# mixer_module.net
KiCad netlist of a schematic drawn in EAGLE
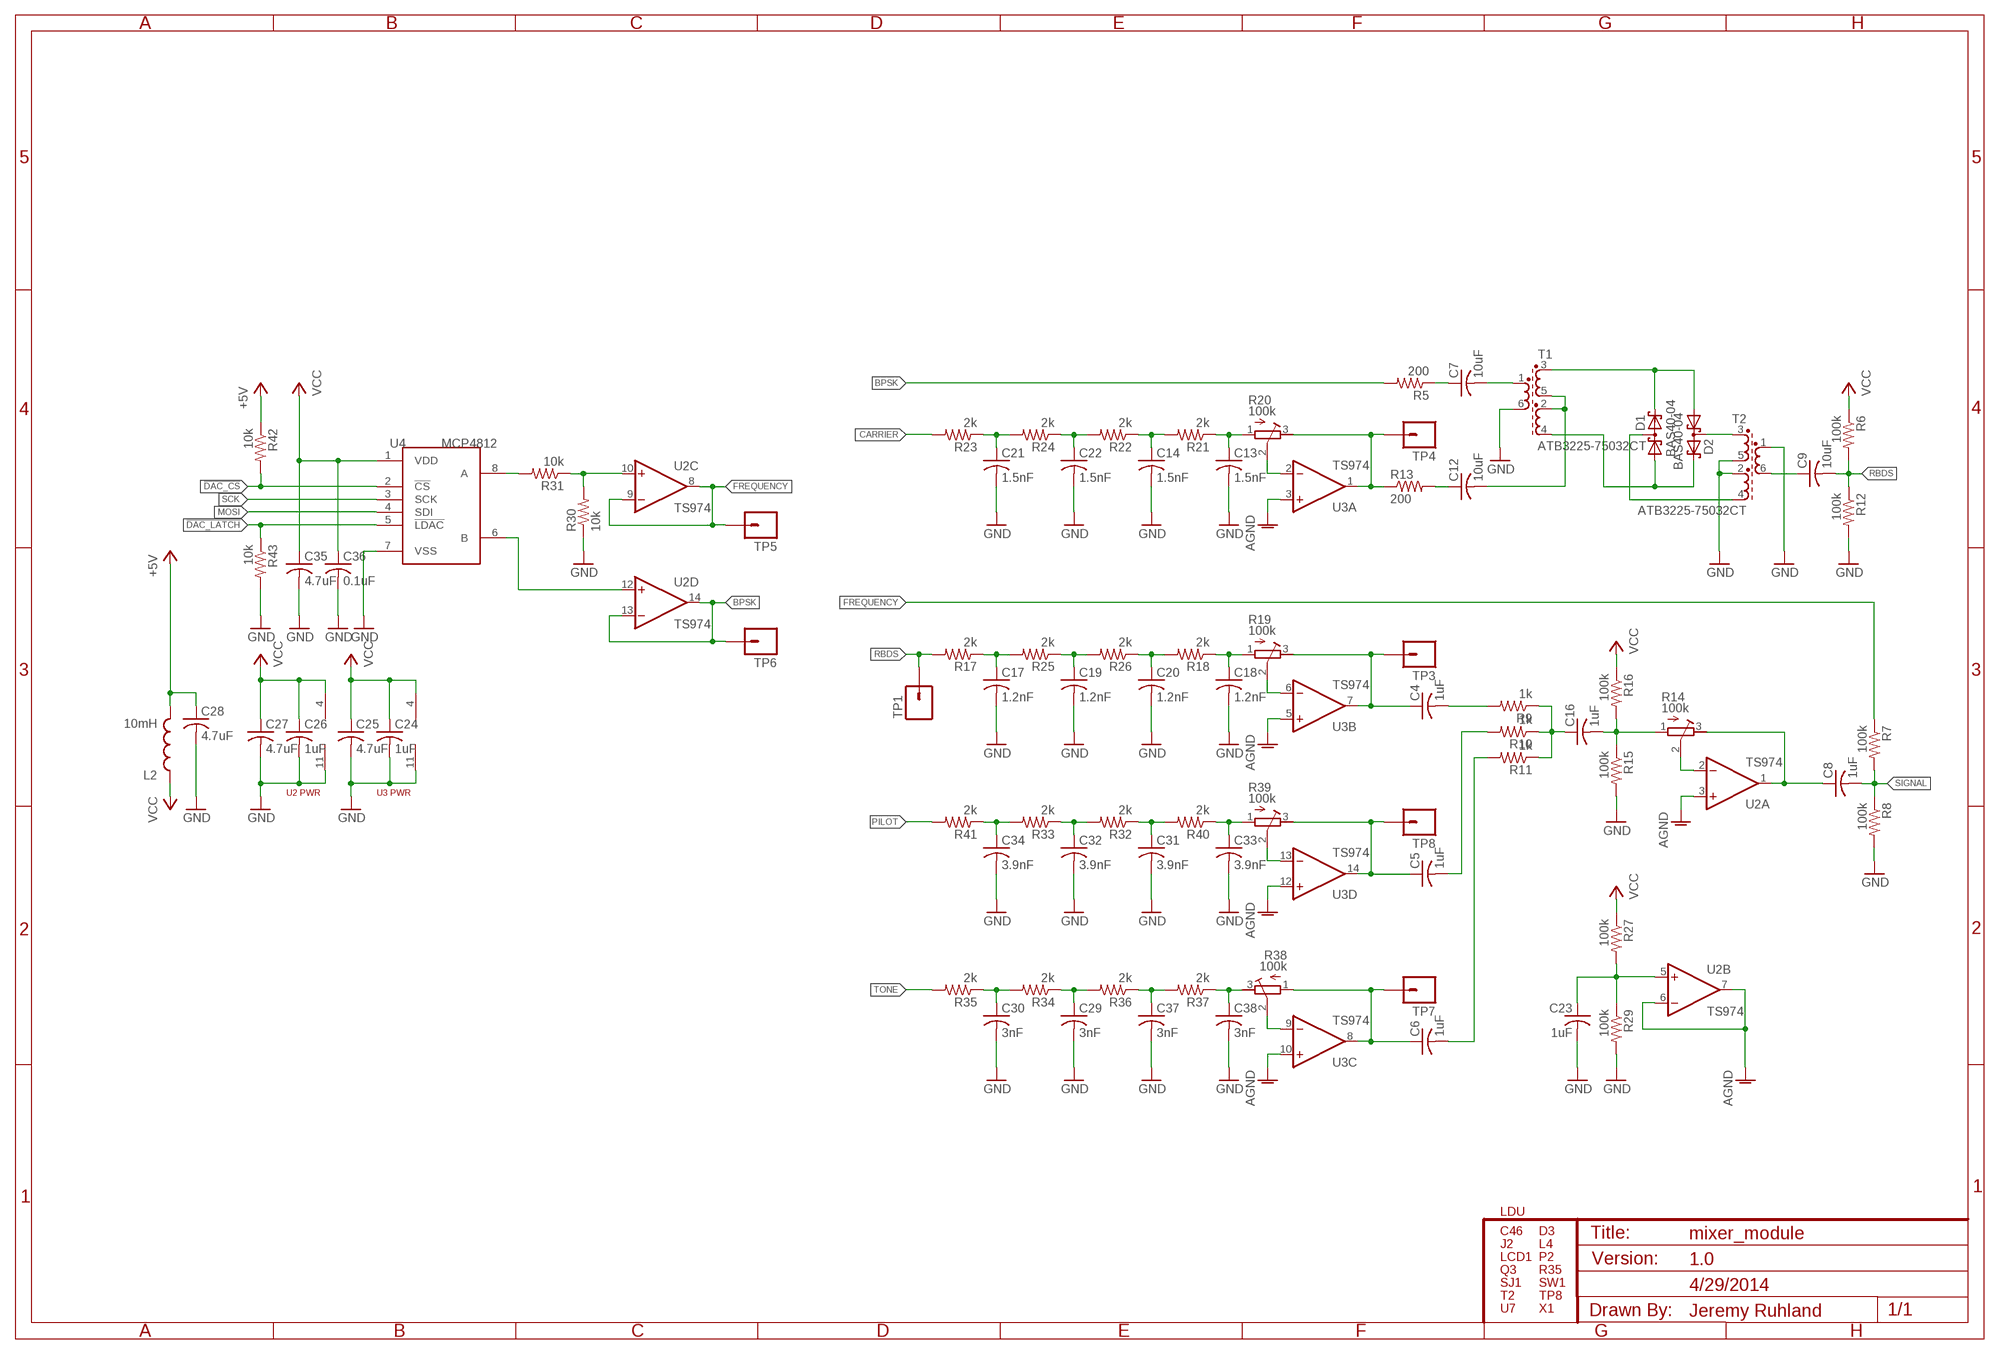
[diagram p0: schematic, sheet 1]

(export (version "E")
  (design (tool "Eeschema 10.0.6"))
  (components
    (comp (ref "C4")
      (value "1uF")
      (footprint "eagle-import:C1206")
      (libsource (lib "eagle-import") (part "C-USC1206"))
    )
    (comp (ref "C5")
      (value "1uF")
      (footprint "eagle-import:C1206")
      (libsource (lib "eagle-import") (part "C-USC1206"))
    )
    (comp (ref "C6")
      (value "1uF")
      (footprint "eagle-import:C1206")
      (libsource (lib "eagle-import") (part "C-USC1206"))
    )
    (comp (ref "C7")
      (value "10uF")
      (footprint "eagle-import:C1206")
      (libsource (lib "eagle-import") (part "C-USC1206"))
    )
    (comp (ref "C8")
      (value "1uF")
      (footprint "eagle-import:C1206")
      (libsource (lib "eagle-import") (part "C-USC1206"))
    )
    (comp (ref "C9")
      (value "10uF")
      (footprint "eagle-import:C1206")
      (libsource (lib "eagle-import") (part "C-USC1206"))
    )
    (comp (ref "C12")
      (value "10uF")
      (footprint "eagle-import:C1206")
      (libsource (lib "eagle-import") (part "C-USC1206"))
    )
    (comp (ref "C13")
      (value "1.5nF")
      (footprint "eagle-import:C1206")
      (libsource (lib "eagle-import") (part "C-USC1206"))
    )
    (comp (ref "C14")
      (value "1.5nF")
      (footprint "eagle-import:C1206")
      (libsource (lib "eagle-import") (part "C-USC1206"))
    )
    (comp (ref "C16")
      (value "1uF")
      (footprint "eagle-import:C1206")
      (libsource (lib "eagle-import") (part "C-USC1206"))
    )
    (comp (ref "C17")
      (value "1.2nF")
      (footprint "eagle-import:C1206")
      (libsource (lib "eagle-import") (part "C-USC1206"))
    )
    (comp (ref "C18")
      (value "1.2nF")
      (footprint "eagle-import:C1206")
      (libsource (lib "eagle-import") (part "C-USC1206"))
    )
    (comp (ref "C19")
      (value "1.2nF")
      (footprint "eagle-import:C1206")
      (libsource (lib "eagle-import") (part "C-USC1206"))
    )
    (comp (ref "C20")
      (value "1.2nF")
      (footprint "eagle-import:C1206")
      (libsource (lib "eagle-import") (part "C-USC1206"))
    )
    (comp (ref "C21")
      (value "1.5nF")
      (footprint "eagle-import:C1206")
      (libsource (lib "eagle-import") (part "C-USC1206"))
    )
    (comp (ref "C22")
      (value "1.5nF")
      (footprint "eagle-import:C1206")
      (libsource (lib "eagle-import") (part "C-USC1206"))
    )
    (comp (ref "C23")
      (value "1uF")
      (footprint "eagle-import:C1206")
      (libsource (lib "eagle-import") (part "C-USC1206"))
    )
    (comp (ref "C24")
      (value "1uF")
      (footprint "eagle-import:C1206")
      (libsource (lib "eagle-import") (part "C-USC1206"))
    )
    (comp (ref "C25")
      (value "4.7uF")
      (footprint "eagle-import:C1206")
      (libsource (lib "eagle-import") (part "C-USC1206"))
    )
    (comp (ref "C26")
      (value "1uF")
      (footprint "eagle-import:C1206")
      (libsource (lib "eagle-import") (part "C-USC1206"))
    )
    (comp (ref "C27")
      (value "4.7uF")
      (footprint "eagle-import:C1206")
      (libsource (lib "eagle-import") (part "C-USC1206"))
    )
    (comp (ref "C28")
      (value "4.7uF")
      (footprint "eagle-import:C1206")
      (libsource (lib "eagle-import") (part "C-USC1206"))
    )
    (comp (ref "C29")
      (value "3nF")
      (footprint "eagle-import:C1206")
      (libsource (lib "eagle-import") (part "C-USC1206"))
    )
    (comp (ref "C30")
      (value "3nF")
      (footprint "eagle-import:C1206")
      (libsource (lib "eagle-import") (part "C-USC1206"))
    )
    (comp (ref "C31")
      (value "3.9nF")
      (footprint "eagle-import:C1206")
      (libsource (lib "eagle-import") (part "C-USC1206"))
    )
    (comp (ref "C32")
      (value "3.9nF")
      (footprint "eagle-import:C1206")
      (libsource (lib "eagle-import") (part "C-USC1206"))
    )
    (comp (ref "C33")
      (value "3.9nF")
      (footprint "eagle-import:C1206")
      (libsource (lib "eagle-import") (part "C-USC1206"))
    )
    (comp (ref "C34")
      (value "3.9nF")
      (footprint "eagle-import:C1206")
      (libsource (lib "eagle-import") (part "C-USC1206"))
    )
    (comp (ref "C35")
      (value "4.7uF")
      (footprint "eagle-import:C1206")
      (libsource (lib "eagle-import") (part "C-USC1206"))
    )
    (comp (ref "C36")
      (value "0.1uF")
      (footprint "eagle-import:C1206")
      (libsource (lib "eagle-import") (part "C-USC1206"))
    )
    (comp (ref "C37")
      (value "3nF")
      (footprint "eagle-import:C1206")
      (libsource (lib "eagle-import") (part "C-USC1206"))
    )
    (comp (ref "C38")
      (value "3nF")
      (footprint "eagle-import:C1206")
      (libsource (lib "eagle-import") (part "C-USC1206"))
    )
    (comp (ref "D1")
      (value "BAS40-04")
      (footprint "eagle-import:SOT23")
      (libsource (lib "eagle-import") (part "BAS40-04"))
    )
    (comp (ref "D2")
      (value "BAS40-04")
      (footprint "eagle-import:SOT23")
      (libsource (lib "eagle-import") (part "BAS40-04"))
    )
    (comp (ref "L2")
      (value "10mH")
      (footprint "eagle-import:1210")
      (libsource (lib "eagle-import") (part "INDUCTOR1210"))
    )
    (comp (ref "R5")
      (value "200")
      (footprint "eagle-import:R1206")
      (libsource (lib "eagle-import") (part "R-US_R1206"))
    )
    (comp (ref "R6")
      (value "100k")
      (footprint "eagle-import:R1206")
      (libsource (lib "eagle-import") (part "R-US_R1206"))
    )
    (comp (ref "R7")
      (value "100k")
      (footprint "eagle-import:R1206")
      (libsource (lib "eagle-import") (part "R-US_R1206"))
    )
    (comp (ref "R8")
      (value "100k")
      (footprint "eagle-import:R1206")
      (libsource (lib "eagle-import") (part "R-US_R1206"))
    )
    (comp (ref "R9")
      (value "1k")
      (footprint "eagle-import:R1206")
      (libsource (lib "eagle-import") (part "R-US_R1206"))
    )
    (comp (ref "R10")
      (value "1k")
      (footprint "eagle-import:R1206")
      (libsource (lib "eagle-import") (part "R-US_R1206"))
    )
    (comp (ref "R11")
      (value "1k")
      (footprint "eagle-import:R1206")
      (libsource (lib "eagle-import") (part "R-US_R1206"))
    )
    (comp (ref "R12")
      (value "100k")
      (footprint "eagle-import:R1206")
      (libsource (lib "eagle-import") (part "R-US_R1206"))
    )
    (comp (ref "R13")
      (value "200")
      (footprint "eagle-import:R1206")
      (libsource (lib "eagle-import") (part "R-US_R1206"))
    )
    (comp (ref "R14")
      (value "100k")
      (footprint "eagle-import:RTRIM3304W")
      (libsource (lib "eagle-import") (part "R-TRIMM3304W"))
    )
    (comp (ref "R15")
      (value "100k")
      (footprint "eagle-import:R1206")
      (libsource (lib "eagle-import") (part "R-US_R1206"))
    )
    (comp (ref "R16")
      (value "100k")
      (footprint "eagle-import:R1206")
      (libsource (lib "eagle-import") (part "R-US_R1206"))
    )
    (comp (ref "R17")
      (value "2k")
      (footprint "eagle-import:R1206")
      (libsource (lib "eagle-import") (part "R-US_R1206"))
    )
    (comp (ref "R18")
      (value "2k")
      (footprint "eagle-import:R1206")
      (libsource (lib "eagle-import") (part "R-US_R1206"))
    )
    (comp (ref "R19")
      (value "100k")
      (footprint "eagle-import:RTRIM3304W")
      (libsource (lib "eagle-import") (part "R-TRIMM3304W"))
    )
    (comp (ref "R20")
      (value "100k")
      (footprint "eagle-import:RTRIM3304W")
      (libsource (lib "eagle-import") (part "R-TRIMM3304W"))
    )
    (comp (ref "R21")
      (value "2k")
      (footprint "eagle-import:R1206")
      (libsource (lib "eagle-import") (part "R-US_R1206"))
    )
    (comp (ref "R22")
      (value "2k")
      (footprint "eagle-import:R1206")
      (libsource (lib "eagle-import") (part "R-US_R1206"))
    )
    (comp (ref "R23")
      (value "2k")
      (footprint "eagle-import:R1206")
      (libsource (lib "eagle-import") (part "R-US_R1206"))
    )
    (comp (ref "R24")
      (value "2k")
      (footprint "eagle-import:R1206")
      (libsource (lib "eagle-import") (part "R-US_R1206"))
    )
    (comp (ref "R25")
      (value "2k")
      (footprint "eagle-import:R1206")
      (libsource (lib "eagle-import") (part "R-US_R1206"))
    )
    (comp (ref "R26")
      (value "2k")
      (footprint "eagle-import:R1206")
      (libsource (lib "eagle-import") (part "R-US_R1206"))
    )
    (comp (ref "R27")
      (value "100k")
      (footprint "eagle-import:R1206")
      (libsource (lib "eagle-import") (part "R-US_R1206"))
    )
    (comp (ref "R29")
      (value "100k")
      (footprint "eagle-import:R1206")
      (libsource (lib "eagle-import") (part "R-US_R1206"))
    )
    (comp (ref "R30")
      (value "10k")
      (footprint "eagle-import:R1206")
      (libsource (lib "eagle-import") (part "R-US_R1206"))
    )
    (comp (ref "R31")
      (value "10k")
      (footprint "eagle-import:R1206")
      (libsource (lib "eagle-import") (part "R-US_R1206"))
    )
    (comp (ref "R32")
      (value "2k")
      (footprint "eagle-import:R1206")
      (libsource (lib "eagle-import") (part "R-US_R1206"))
    )
    (comp (ref "R33")
      (value "2k")
      (footprint "eagle-import:R1206")
      (libsource (lib "eagle-import") (part "R-US_R1206"))
    )
    (comp (ref "R34")
      (value "2k")
      (footprint "eagle-import:R1206")
      (libsource (lib "eagle-import") (part "R-US_R1206"))
    )
    (comp (ref "R35")
      (value "2k")
      (footprint "eagle-import:R1206")
      (libsource (lib "eagle-import") (part "R-US_R1206"))
    )
    (comp (ref "R36")
      (value "2k")
      (footprint "eagle-import:R1206")
      (libsource (lib "eagle-import") (part "R-US_R1206"))
    )
    (comp (ref "R37")
      (value "2k")
      (footprint "eagle-import:R1206")
      (libsource (lib "eagle-import") (part "R-US_R1206"))
    )
    (comp (ref "R38")
      (value "100k")
      (footprint "eagle-import:RTRIM3304W")
      (libsource (lib "eagle-import") (part "R-TRIMM3304W"))
    )
    (comp (ref "R39")
      (value "100k")
      (footprint "eagle-import:RTRIM3304W")
      (libsource (lib "eagle-import") (part "R-TRIMM3304W"))
    )
    (comp (ref "R40")
      (value "2k")
      (footprint "eagle-import:R1206")
      (libsource (lib "eagle-import") (part "R-US_R1206"))
    )
    (comp (ref "R41")
      (value "2k")
      (footprint "eagle-import:R1206")
      (libsource (lib "eagle-import") (part "R-US_R1206"))
    )
    (comp (ref "R42")
      (value "10k")
      (footprint "eagle-import:R1206")
      (libsource (lib "eagle-import") (part "R-US_R1206"))
    )
    (comp (ref "R43")
      (value "10k")
      (footprint "eagle-import:R1206")
      (libsource (lib "eagle-import") (part "R-US_R1206"))
    )
    (comp (ref "T1")
      (value "ATB3225-75032CT")
      (footprint "eagle-import:TRANS")
      (libsource (lib "eagle-import") (part "ATB3225-75032CT"))
    )
    (comp (ref "T2")
      (value "ATB3225-75032CT")
      (footprint "eagle-import:TRANS")
      (libsource (lib "eagle-import") (part "ATB3225-75032CT"))
    )
    (comp (ref "TP1")
      (value "M01PTH")
      (footprint "eagle-import:1X01")
      (libsource (lib "eagle-import") (part "M01PTH"))
    )
    (comp (ref "TP3")
      (value "M01PTH")
      (footprint "eagle-import:1X01")
      (libsource (lib "eagle-import") (part "M01PTH"))
    )
    (comp (ref "TP4")
      (value "M01PTH")
      (footprint "eagle-import:1X01")
      (libsource (lib "eagle-import") (part "M01PTH"))
    )
    (comp (ref "TP5")
      (value "M01PTH")
      (footprint "eagle-import:1X01")
      (libsource (lib "eagle-import") (part "M01PTH"))
    )
    (comp (ref "TP6")
      (value "M01PTH")
      (footprint "eagle-import:1X01")
      (libsource (lib "eagle-import") (part "M01PTH"))
    )
    (comp (ref "TP7")
      (value "M01PTH")
      (footprint "eagle-import:1X01")
      (libsource (lib "eagle-import") (part "M01PTH"))
    )
    (comp (ref "TP8")
      (value "M01PTH")
      (footprint "eagle-import:1X01")
      (libsource (lib "eagle-import") (part "M01PTH"))
    )
    (comp (ref "U2")
      (value "TS974")
      (footprint "eagle-import:SO14")
      (libsource (lib "eagle-import") (part "OPA4743UA"))
    )
    (comp (ref "U3")
      (value "TS974")
      (footprint "eagle-import:SO14")
      (libsource (lib "eagle-import") (part "OPA4743UA"))
    )
    (comp (ref "U4")
      (value "MCP4812")
      (footprint "eagle-import:SO-08")
      (libsource (lib "eagle-import") (part "MCP4812"))
    )
  )
  (nets
    (net (code "1") (name "+5V") (class "Default")
      (node (ref "C28") (pin "1") (pinfunction "1_1") (pintype "passive"))
      (node (ref "L2") (pin "2") (pinfunction "2_2") (pintype "passive"))
      (node (ref "R42") (pin "1") (pinfunction "1_1") (pintype "passive"))
    )
    (net (code "2") (name "/~{DAC_CS}") (class "Default")
      (node (ref "R42") (pin "2") (pinfunction "2_2") (pintype "passive"))
      (node (ref "U4") (pin "2") (pinfunction "~{CS}_2") (pintype "bidirectional"))
    )
    (net (code "3") (name "/~{DAC_LATCH}") (class "Default")
      (node (ref "R43") (pin "1") (pinfunction "1_1") (pintype "passive"))
      (node (ref "U4") (pin "5") (pinfunction "~{LDAC}_5") (pintype "bidirectional"))
    )
    (net (code "4") (name "AGND") (class "Default")
      (node (ref "U2") (pin "3") (pinfunction "+IN_3") (pintype "input"))
      (node (ref "U2") (pin "6") (pinfunction "-IN_6") (pintype "input"))
      (node (ref "U2") (pin "7") (pinfunction "OUT_7") (pintype "output"))
      (node (ref "U3") (pin "10") (pinfunction "+IN_10") (pintype "input"))
      (node (ref "U3") (pin "12") (pinfunction "+IN_12") (pintype "input"))
      (node (ref "U3") (pin "3") (pinfunction "+IN_3") (pintype "input"))
      (node (ref "U3") (pin "5") (pinfunction "+IN_5") (pintype "input"))
    )
    (net (code "5") (name "BPSK") (class "Default")
      (node (ref "R5") (pin "2") (pinfunction "2_2") (pintype "passive"))
      (node (ref "TP6") (pin "1") (pinfunction "1_1") (pintype "passive"))
      (node (ref "U2") (pin "13") (pinfunction "-IN_13") (pintype "input"))
      (node (ref "U2") (pin "14") (pinfunction "OUT_14") (pintype "output"))
    )
    (net (code "6") (name "CARRIER") (class "Default")
      (node (ref "R23") (pin "2") (pinfunction "2_2") (pintype "passive"))
    )
    (net (code "7") (name "FREQUENCY") (class "Default")
      (node (ref "R7") (pin "1") (pinfunction "1_1") (pintype "passive"))
      (node (ref "TP5") (pin "1") (pinfunction "1_1") (pintype "passive"))
      (node (ref "U2") (pin "8") (pinfunction "OUT_8") (pintype "output"))
      (node (ref "U2") (pin "9") (pinfunction "-IN_9") (pintype "input"))
    )
    (net (code "8") (name "GND") (class "Default")
      (node (ref "C13") (pin "2") (pinfunction "2_2") (pintype "passive"))
      (node (ref "C14") (pin "2") (pinfunction "2_2") (pintype "passive"))
      (node (ref "C17") (pin "2") (pinfunction "2_2") (pintype "passive"))
      (node (ref "C18") (pin "2") (pinfunction "2_2") (pintype "passive"))
      (node (ref "C19") (pin "2") (pinfunction "2_2") (pintype "passive"))
      (node (ref "C20") (pin "2") (pinfunction "2_2") (pintype "passive"))
      (node (ref "C21") (pin "2") (pinfunction "2_2") (pintype "passive"))
      (node (ref "C22") (pin "2") (pinfunction "2_2") (pintype "passive"))
      (node (ref "C23") (pin "2") (pinfunction "2_2") (pintype "passive"))
      (node (ref "C24") (pin "2") (pinfunction "2_2") (pintype "passive"))
      (node (ref "C25") (pin "2") (pinfunction "2_2") (pintype "passive"))
      (node (ref "C26") (pin "2") (pinfunction "2_2") (pintype "passive"))
      (node (ref "C27") (pin "2") (pinfunction "2_2") (pintype "passive"))
      (node (ref "C28") (pin "2") (pinfunction "2_2") (pintype "passive"))
      (node (ref "C29") (pin "2") (pinfunction "2_2") (pintype "passive"))
      (node (ref "C30") (pin "2") (pinfunction "2_2") (pintype "passive"))
      (node (ref "C31") (pin "2") (pinfunction "2_2") (pintype "passive"))
      (node (ref "C32") (pin "2") (pinfunction "2_2") (pintype "passive"))
      (node (ref "C33") (pin "2") (pinfunction "2_2") (pintype "passive"))
      (node (ref "C34") (pin "2") (pinfunction "2_2") (pintype "passive"))
      (node (ref "C35") (pin "2") (pinfunction "2_2") (pintype "passive"))
      (node (ref "C36") (pin "2") (pinfunction "2_2") (pintype "passive"))
      (node (ref "C37") (pin "2") (pinfunction "2_2") (pintype "passive"))
      (node (ref "C38") (pin "2") (pinfunction "2_2") (pintype "passive"))
      (node (ref "R12") (pin "2") (pinfunction "2_2") (pintype "passive"))
      (node (ref "R15") (pin "2") (pinfunction "2_2") (pintype "passive"))
      (node (ref "R29") (pin "2") (pinfunction "2_2") (pintype "passive"))
      (node (ref "R30") (pin "1") (pinfunction "1_1") (pintype "passive"))
      (node (ref "R43") (pin "2") (pinfunction "2_2") (pintype "passive"))
      (node (ref "R8") (pin "2") (pinfunction "2_2") (pintype "passive"))
      (node (ref "T1") (pin "6") (pinfunction "6_6") (pintype "passive"))
      (node (ref "T2") (pin "1") (pinfunction "1_1") (pintype "passive"))
      (node (ref "T2") (pin "2") (pinfunction "2_2") (pintype "passive"))
      (node (ref "T2") (pin "5") (pinfunction "5_5") (pintype "passive"))
      (node (ref "U2") (pin "11") (pinfunction "V-_11") (pintype "power_in"))
      (node (ref "U3") (pin "11") (pinfunction "V-_11") (pintype "power_in"))
      (node (ref "U4") (pin "7") (pinfunction "VSS_7") (pintype "bidirectional"))
    )
    (net (code "9") (name "MOSI") (class "Default")
      (node (ref "U4") (pin "4") (pinfunction "SDI_4") (pintype "bidirectional"))
    )
    (net (code "10") (name "Net-(C4-Pad2)") (class "Default")
      (node (ref "C4") (pin "2") (pinfunction "2_2") (pintype "passive"))
      (node (ref "R9") (pin "2") (pinfunction "2_2") (pintype "passive"))
    )
    (net (code "11") (name "Net-(C5-Pad2)") (class "Default")
      (node (ref "C5") (pin "2") (pinfunction "2_2") (pintype "passive"))
      (node (ref "R10") (pin "2") (pinfunction "2_2") (pintype "passive"))
    )
    (net (code "12") (name "Net-(C6-Pad2)") (class "Default")
      (node (ref "C6") (pin "2") (pinfunction "2_2") (pintype "passive"))
      (node (ref "R11") (pin "2") (pinfunction "2_2") (pintype "passive"))
    )
    (net (code "13") (name "Net-(C7-Pad1)") (class "Default")
      (node (ref "C7") (pin "1") (pinfunction "1_1") (pintype "passive"))
      (node (ref "R5") (pin "1") (pinfunction "1_1") (pintype "passive"))
    )
    (net (code "14") (name "Net-(C7-Pad2)") (class "Default")
      (node (ref "C7") (pin "2") (pinfunction "2_2") (pintype "passive"))
      (node (ref "T1") (pin "1") (pinfunction "1_1") (pintype "passive"))
    )
    (net (code "15") (name "Net-(C9-Pad1)") (class "Default")
      (node (ref "C9") (pin "1") (pinfunction "1_1") (pintype "passive"))
      (node (ref "T2") (pin "6") (pinfunction "6_6") (pintype "passive"))
    )
    (net (code "16") (name "Net-(C12-Pad1)") (class "Default")
      (node (ref "C12") (pin "1") (pinfunction "1_1") (pintype "passive"))
      (node (ref "R13") (pin "2") (pinfunction "2_2") (pintype "passive"))
    )
    (net (code "17") (name "Net-(C12-Pad2)") (class "Default")
      (node (ref "C12") (pin "2") (pinfunction "2_2") (pintype "passive"))
      (node (ref "T1") (pin "2") (pinfunction "2_2") (pintype "passive"))
      (node (ref "T1") (pin "5") (pinfunction "5_5") (pintype "passive"))
    )
    (net (code "18") (name "Net-(C14-Pad1)") (class "Default")
      (node (ref "C14") (pin "1") (pinfunction "1_1") (pintype "passive"))
      (node (ref "R21") (pin "2") (pinfunction "2_2") (pintype "passive"))
      (node (ref "R22") (pin "1") (pinfunction "1_1") (pintype "passive"))
    )
    (net (code "19") (name "Net-(C16-Pad1)") (class "Default")
      (node (ref "C16") (pin "1") (pinfunction "1_1") (pintype "passive"))
      (node (ref "R10") (pin "1") (pinfunction "1_1") (pintype "passive"))
      (node (ref "R11") (pin "1") (pinfunction "1_1") (pintype "passive"))
      (node (ref "R9") (pin "1") (pinfunction "1_1") (pintype "passive"))
    )
    (net (code "20") (name "Net-(C17-Pad1)") (class "Default")
      (node (ref "C17") (pin "1") (pinfunction "1_1") (pintype "passive"))
      (node (ref "R17") (pin "1") (pinfunction "1_1") (pintype "passive"))
      (node (ref "R25") (pin "2") (pinfunction "2_2") (pintype "passive"))
    )
    (net (code "21") (name "Net-(C19-Pad1)") (class "Default")
      (node (ref "C19") (pin "1") (pinfunction "1_1") (pintype "passive"))
      (node (ref "R25") (pin "1") (pinfunction "1_1") (pintype "passive"))
      (node (ref "R26") (pin "2") (pinfunction "2_2") (pintype "passive"))
    )
    (net (code "22") (name "Net-(C20-Pad1)") (class "Default")
      (node (ref "C20") (pin "1") (pinfunction "1_1") (pintype "passive"))
      (node (ref "R18") (pin "2") (pinfunction "2_2") (pintype "passive"))
      (node (ref "R26") (pin "1") (pinfunction "1_1") (pintype "passive"))
    )
    (net (code "23") (name "Net-(C21-Pad1)") (class "Default")
      (node (ref "C21") (pin "1") (pinfunction "1_1") (pintype "passive"))
      (node (ref "R23") (pin "1") (pinfunction "1_1") (pintype "passive"))
      (node (ref "R24") (pin "2") (pinfunction "2_2") (pintype "passive"))
    )
    (net (code "24") (name "Net-(C22-Pad1)") (class "Default")
      (node (ref "C22") (pin "1") (pinfunction "1_1") (pintype "passive"))
      (node (ref "R22") (pin "2") (pinfunction "2_2") (pintype "passive"))
      (node (ref "R24") (pin "1") (pinfunction "1_1") (pintype "passive"))
    )
    (net (code "25") (name "Net-(C29-Pad1)") (class "Default")
      (node (ref "C29") (pin "1") (pinfunction "1_1") (pintype "passive"))
      (node (ref "R34") (pin "1") (pinfunction "1_1") (pintype "passive"))
      (node (ref "R36") (pin "2") (pinfunction "2_2") (pintype "passive"))
    )
    (net (code "26") (name "Net-(C30-Pad1)") (class "Default")
      (node (ref "C30") (pin "1") (pinfunction "1_1") (pintype "passive"))
      (node (ref "R34") (pin "2") (pinfunction "2_2") (pintype "passive"))
      (node (ref "R35") (pin "1") (pinfunction "1_1") (pintype "passive"))
    )
    (net (code "27") (name "Net-(C31-Pad1)") (class "Default")
      (node (ref "C31") (pin "1") (pinfunction "1_1") (pintype "passive"))
      (node (ref "R32") (pin "1") (pinfunction "1_1") (pintype "passive"))
      (node (ref "R40") (pin "2") (pinfunction "2_2") (pintype "passive"))
    )
    (net (code "28") (name "Net-(C32-Pad1)") (class "Default")
      (node (ref "C32") (pin "1") (pinfunction "1_1") (pintype "passive"))
      (node (ref "R32") (pin "2") (pinfunction "2_2") (pintype "passive"))
      (node (ref "R33") (pin "1") (pinfunction "1_1") (pintype "passive"))
    )
    (net (code "29") (name "Net-(C34-Pad1)") (class "Default")
      (node (ref "C34") (pin "1") (pinfunction "1_1") (pintype "passive"))
      (node (ref "R33") (pin "2") (pinfunction "2_2") (pintype "passive"))
      (node (ref "R41") (pin "1") (pinfunction "1_1") (pintype "passive"))
    )
    (net (code "30") (name "Net-(C37-Pad1)") (class "Default")
      (node (ref "C37") (pin "1") (pinfunction "1_1") (pintype "passive"))
      (node (ref "R36") (pin "1") (pinfunction "1_1") (pintype "passive"))
      (node (ref "R37") (pin "2") (pinfunction "2_2") (pintype "passive"))
    )
    (net (code "31") (name "Net-(D1-A1)") (class "Default")
      (node (ref "D1") (pin "1") (pinfunction "A1_1") (pintype "passive"))
      (node (ref "D2") (pin "2") (pinfunction "C2_2") (pintype "passive"))
      (node (ref "T1") (pin "4") (pinfunction "4_4") (pintype "passive"))
    )
    (net (code "32") (name "Net-(D1-C1A2)") (class "Default")
      (node (ref "D1") (pin "3") (pinfunction "C1A2_3") (pintype "passive"))
      (node (ref "T2") (pin "4") (pinfunction "4_4") (pintype "passive"))
    )
    (net (code "33") (name "Net-(D1-C2)") (class "Default")
      (node (ref "D1") (pin "2") (pinfunction "C2_2") (pintype "passive"))
      (node (ref "D2") (pin "1") (pinfunction "A1_1") (pintype "passive"))
      (node (ref "T1") (pin "3") (pinfunction "3_3") (pintype "passive"))
    )
    (net (code "34") (name "Net-(D2-C1A2)") (class "Default")
      (node (ref "D2") (pin "3") (pinfunction "C1A2_3") (pintype "passive"))
      (node (ref "T2") (pin "3") (pinfunction "3_3") (pintype "passive"))
    )
    (net (code "35") (name "Net-(R14-A)") (class "Default")
      (node (ref "C16") (pin "2") (pinfunction "2_2") (pintype "passive"))
      (node (ref "R14") (pin "1") (pinfunction "A_1") (pintype "passive"))
      (node (ref "R15") (pin "1") (pinfunction "1_1") (pintype "passive"))
      (node (ref "R16") (pin "2") (pinfunction "2_2") (pintype "passive"))
    )
    (net (code "36") (name "Net-(R14-E)") (class "Default")
      (node (ref "C8") (pin "1") (pinfunction "1_1") (pintype "passive"))
      (node (ref "R14") (pin "3") (pinfunction "E_3") (pintype "passive"))
      (node (ref "U2") (pin "1") (pinfunction "OUT_1") (pintype "output"))
    )
    (net (code "37") (name "Net-(R14-S)") (class "Default")
      (node (ref "R14") (pin "2") (pinfunction "S_2") (pintype "passive"))
      (node (ref "U2") (pin "2") (pinfunction "-IN_2") (pintype "input"))
    )
    (net (code "38") (name "Net-(R19-A)") (class "Default")
      (node (ref "C18") (pin "1") (pinfunction "1_1") (pintype "passive"))
      (node (ref "R18") (pin "1") (pinfunction "1_1") (pintype "passive"))
      (node (ref "R19") (pin "1") (pinfunction "A_1") (pintype "passive"))
    )
    (net (code "39") (name "Net-(R19-E)") (class "Default")
      (node (ref "C4") (pin "1") (pinfunction "1_1") (pintype "passive"))
      (node (ref "R19") (pin "3") (pinfunction "E_3") (pintype "passive"))
      (node (ref "TP3") (pin "1") (pinfunction "1_1") (pintype "passive"))
      (node (ref "U3") (pin "7") (pinfunction "OUT_7") (pintype "output"))
    )
    (net (code "40") (name "Net-(R19-S)") (class "Default")
      (node (ref "R19") (pin "2") (pinfunction "S_2") (pintype "passive"))
      (node (ref "U3") (pin "6") (pinfunction "-IN_6") (pintype "input"))
    )
    (net (code "41") (name "Net-(R20-A)") (class "Default")
      (node (ref "C13") (pin "1") (pinfunction "1_1") (pintype "passive"))
      (node (ref "R20") (pin "1") (pinfunction "A_1") (pintype "passive"))
      (node (ref "R21") (pin "1") (pinfunction "1_1") (pintype "passive"))
    )
    (net (code "42") (name "Net-(R20-E)") (class "Default")
      (node (ref "R13") (pin "1") (pinfunction "1_1") (pintype "passive"))
      (node (ref "R20") (pin "3") (pinfunction "E_3") (pintype "passive"))
      (node (ref "TP4") (pin "1") (pinfunction "1_1") (pintype "passive"))
      (node (ref "U3") (pin "1") (pinfunction "OUT_1") (pintype "output"))
    )
    (net (code "43") (name "Net-(R20-S)") (class "Default")
      (node (ref "R20") (pin "2") (pinfunction "S_2") (pintype "passive"))
      (node (ref "U3") (pin "2") (pinfunction "-IN_2") (pintype "input"))
    )
    (net (code "44") (name "Net-(R38-A)") (class "Default")
      (node (ref "C6") (pin "1") (pinfunction "1_1") (pintype "passive"))
      (node (ref "R38") (pin "1") (pinfunction "A_1") (pintype "passive"))
      (node (ref "TP7") (pin "1") (pinfunction "1_1") (pintype "passive"))
      (node (ref "U3") (pin "8") (pinfunction "OUT_8") (pintype "output"))
    )
    (net (code "45") (name "Net-(R38-E)") (class "Default")
      (node (ref "C38") (pin "1") (pinfunction "1_1") (pintype "passive"))
      (node (ref "R37") (pin "1") (pinfunction "1_1") (pintype "passive"))
      (node (ref "R38") (pin "3") (pinfunction "E_3") (pintype "passive"))
    )
    (net (code "46") (name "Net-(R38-S)") (class "Default")
      (node (ref "R38") (pin "2") (pinfunction "S_2") (pintype "passive"))
      (node (ref "U3") (pin "9") (pinfunction "-IN_9") (pintype "input"))
    )
    (net (code "47") (name "Net-(R39-A)") (class "Default")
      (node (ref "C33") (pin "1") (pinfunction "1_1") (pintype "passive"))
      (node (ref "R39") (pin "1") (pinfunction "A_1") (pintype "passive"))
      (node (ref "R40") (pin "1") (pinfunction "1_1") (pintype "passive"))
    )
    (net (code "48") (name "Net-(R39-E)") (class "Default")
      (node (ref "C5") (pin "1") (pinfunction "1_1") (pintype "passive"))
      (node (ref "R39") (pin "3") (pinfunction "E_3") (pintype "passive"))
      (node (ref "TP8") (pin "1") (pinfunction "1_1") (pintype "passive"))
      (node (ref "U3") (pin "14") (pinfunction "OUT_14") (pintype "output"))
    )
    (net (code "49") (name "Net-(R39-S)") (class "Default")
      (node (ref "R39") (pin "2") (pinfunction "S_2") (pintype "passive"))
      (node (ref "U3") (pin "13") (pinfunction "-IN_13") (pintype "input"))
    )
    (net (code "50") (name "Net-(U2B-+IN)") (class "Default")
      (node (ref "C23") (pin "1") (pinfunction "1_1") (pintype "passive"))
      (node (ref "R27") (pin "2") (pinfunction "2_2") (pintype "passive"))
      (node (ref "R29") (pin "1") (pinfunction "1_1") (pintype "passive"))
      (node (ref "U2") (pin "5") (pinfunction "+IN_5") (pintype "input"))
    )
    (net (code "51") (name "Net-(U2C-+IN)") (class "Default")
      (node (ref "R30") (pin "2") (pinfunction "2_2") (pintype "passive"))
      (node (ref "R31") (pin "1") (pinfunction "1_1") (pintype "passive"))
      (node (ref "U2") (pin "10") (pinfunction "+IN_10") (pintype "input"))
    )
    (net (code "52") (name "Net-(U2D-+IN)") (class "Default")
      (node (ref "U2") (pin "12") (pinfunction "+IN_12") (pintype "input"))
      (node (ref "U4") (pin "6") (pinfunction "B_6") (pintype "bidirectional"))
    )
    (net (code "53") (name "Net-(U4-A)") (class "Default")
      (node (ref "R31") (pin "2") (pinfunction "2_2") (pintype "passive"))
      (node (ref "U4") (pin "8") (pinfunction "A_8") (pintype "bidirectional"))
    )
    (net (code "54") (name "PILOT") (class "Default")
      (node (ref "R41") (pin "2") (pinfunction "2_2") (pintype "passive"))
    )
    (net (code "55") (name "RBDS") (class "Default")
      (node (ref "C9") (pin "2") (pinfunction "2_2") (pintype "passive"))
      (node (ref "R12") (pin "1") (pinfunction "1_1") (pintype "passive"))
      (node (ref "R17") (pin "2") (pinfunction "2_2") (pintype "passive"))
      (node (ref "R6") (pin "2") (pinfunction "2_2") (pintype "passive"))
      (node (ref "TP1") (pin "1") (pinfunction "1_1") (pintype "passive"))
    )
    (net (code "56") (name "SCK") (class "Default")
      (node (ref "U4") (pin "3") (pinfunction "SCK_3") (pintype "bidirectional"))
    )
    (net (code "57") (name "SIGNAL") (class "Default")
      (node (ref "C8") (pin "2") (pinfunction "2_2") (pintype "passive"))
      (node (ref "R7") (pin "2") (pinfunction "2_2") (pintype "passive"))
      (node (ref "R8") (pin "1") (pinfunction "1_1") (pintype "passive"))
    )
    (net (code "58") (name "TONE") (class "Default")
      (node (ref "R35") (pin "2") (pinfunction "2_2") (pintype "passive"))
    )
    (net (code "59") (name "VCC") (class "Default")
      (node (ref "C24") (pin "1") (pinfunction "1_1") (pintype "passive"))
      (node (ref "C25") (pin "1") (pinfunction "1_1") (pintype "passive"))
      (node (ref "C26") (pin "1") (pinfunction "1_1") (pintype "passive"))
      (node (ref "C27") (pin "1") (pinfunction "1_1") (pintype "passive"))
      (node (ref "C35") (pin "1") (pinfunction "1_1") (pintype "passive"))
      (node (ref "C36") (pin "1") (pinfunction "1_1") (pintype "passive"))
      (node (ref "L2") (pin "1") (pinfunction "1_1") (pintype "passive"))
      (node (ref "R16") (pin "1") (pinfunction "1_1") (pintype "passive"))
      (node (ref "R27") (pin "1") (pinfunction "1_1") (pintype "passive"))
      (node (ref "R6") (pin "1") (pinfunction "1_1") (pintype "passive"))
      (node (ref "U2") (pin "4") (pinfunction "V+_4") (pintype "power_in"))
      (node (ref "U3") (pin "4") (pinfunction "V+_4") (pintype "power_in"))
      (node (ref "U4") (pin "1") (pinfunction "VDD_1") (pintype "bidirectional"))
    )
  )
)
